# board.net
KiCad netlist of a schematic drawn in EAGLE
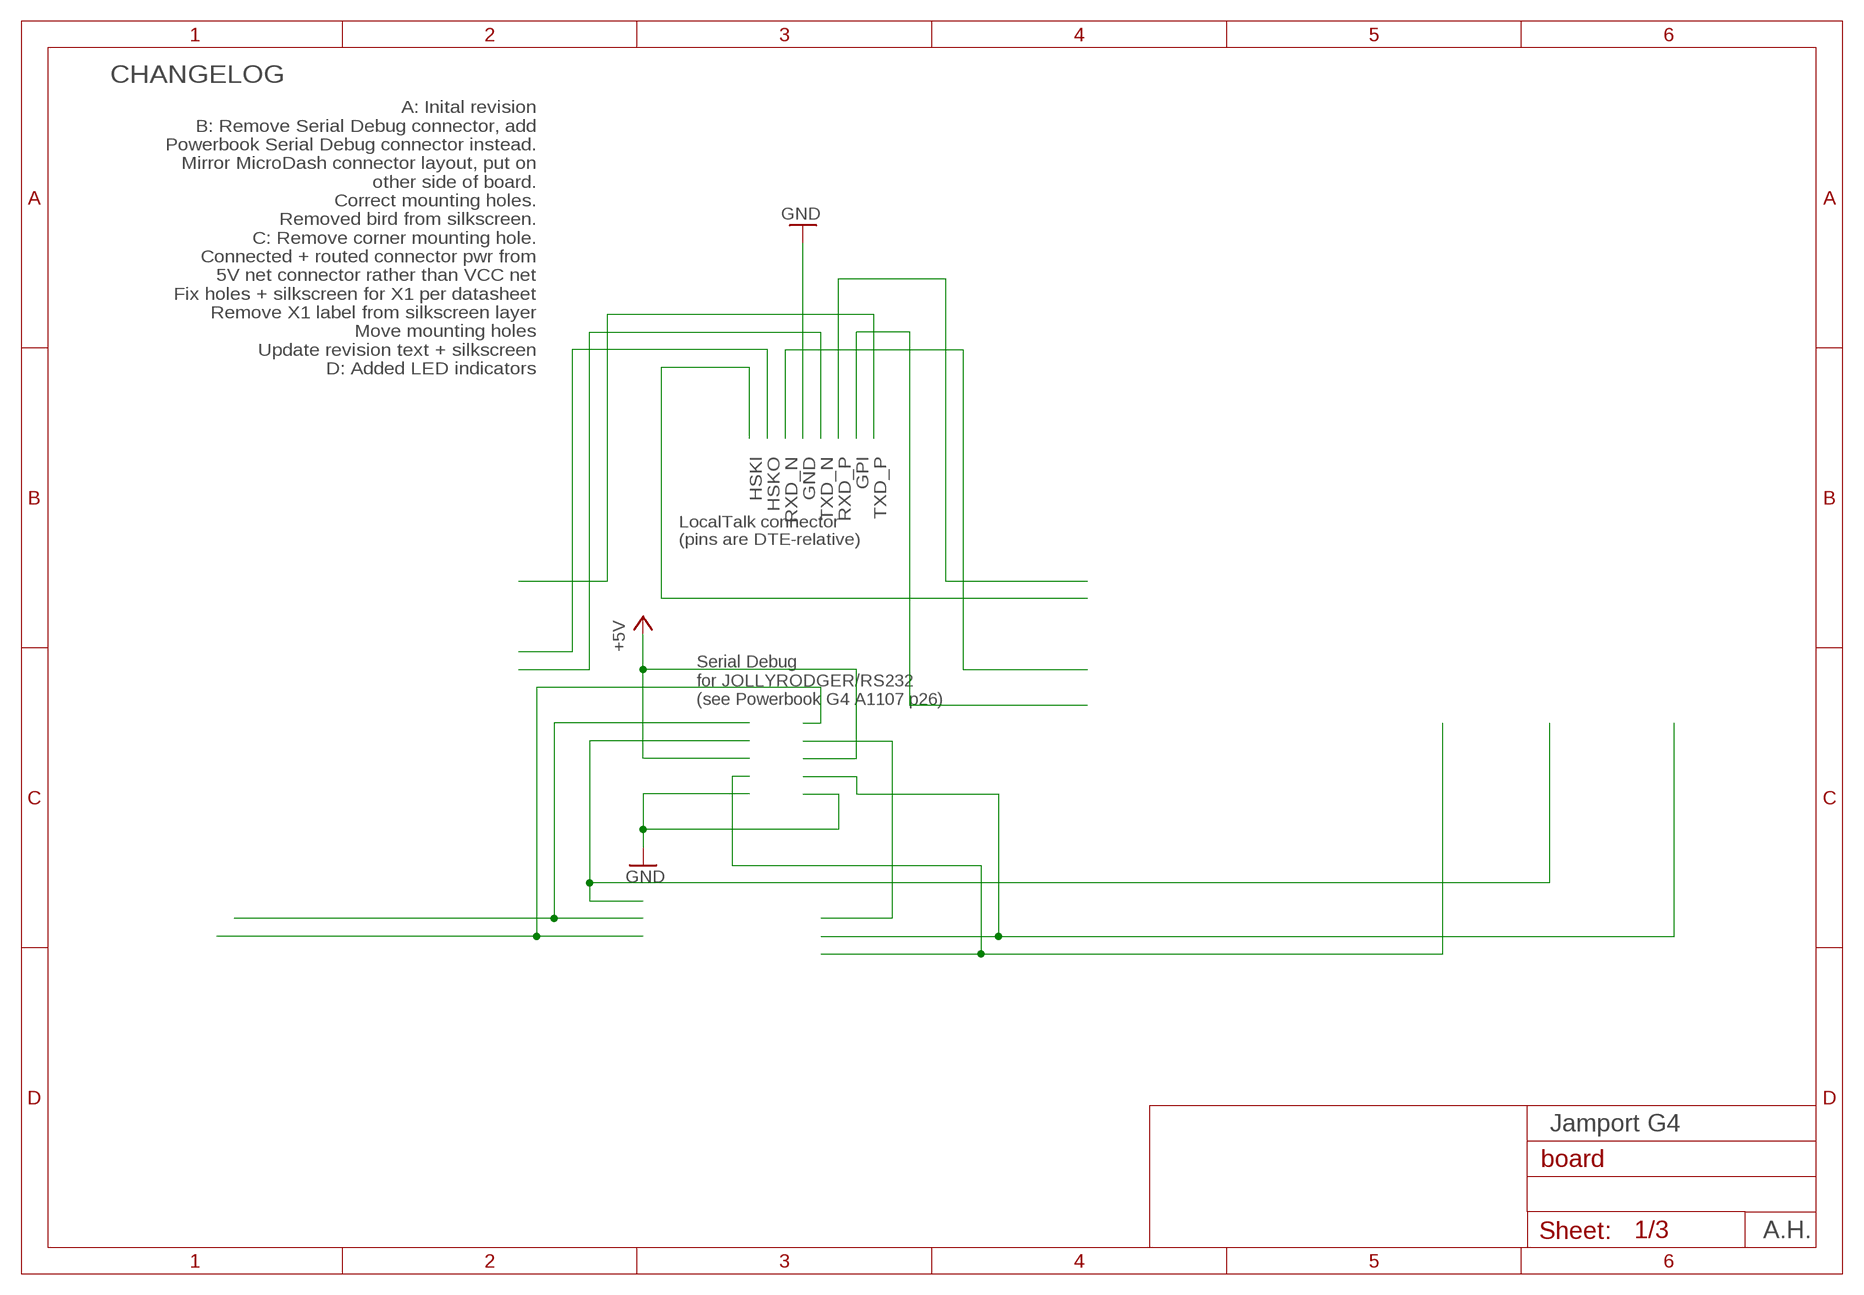
[diagram p0: schematic, sheet 1]
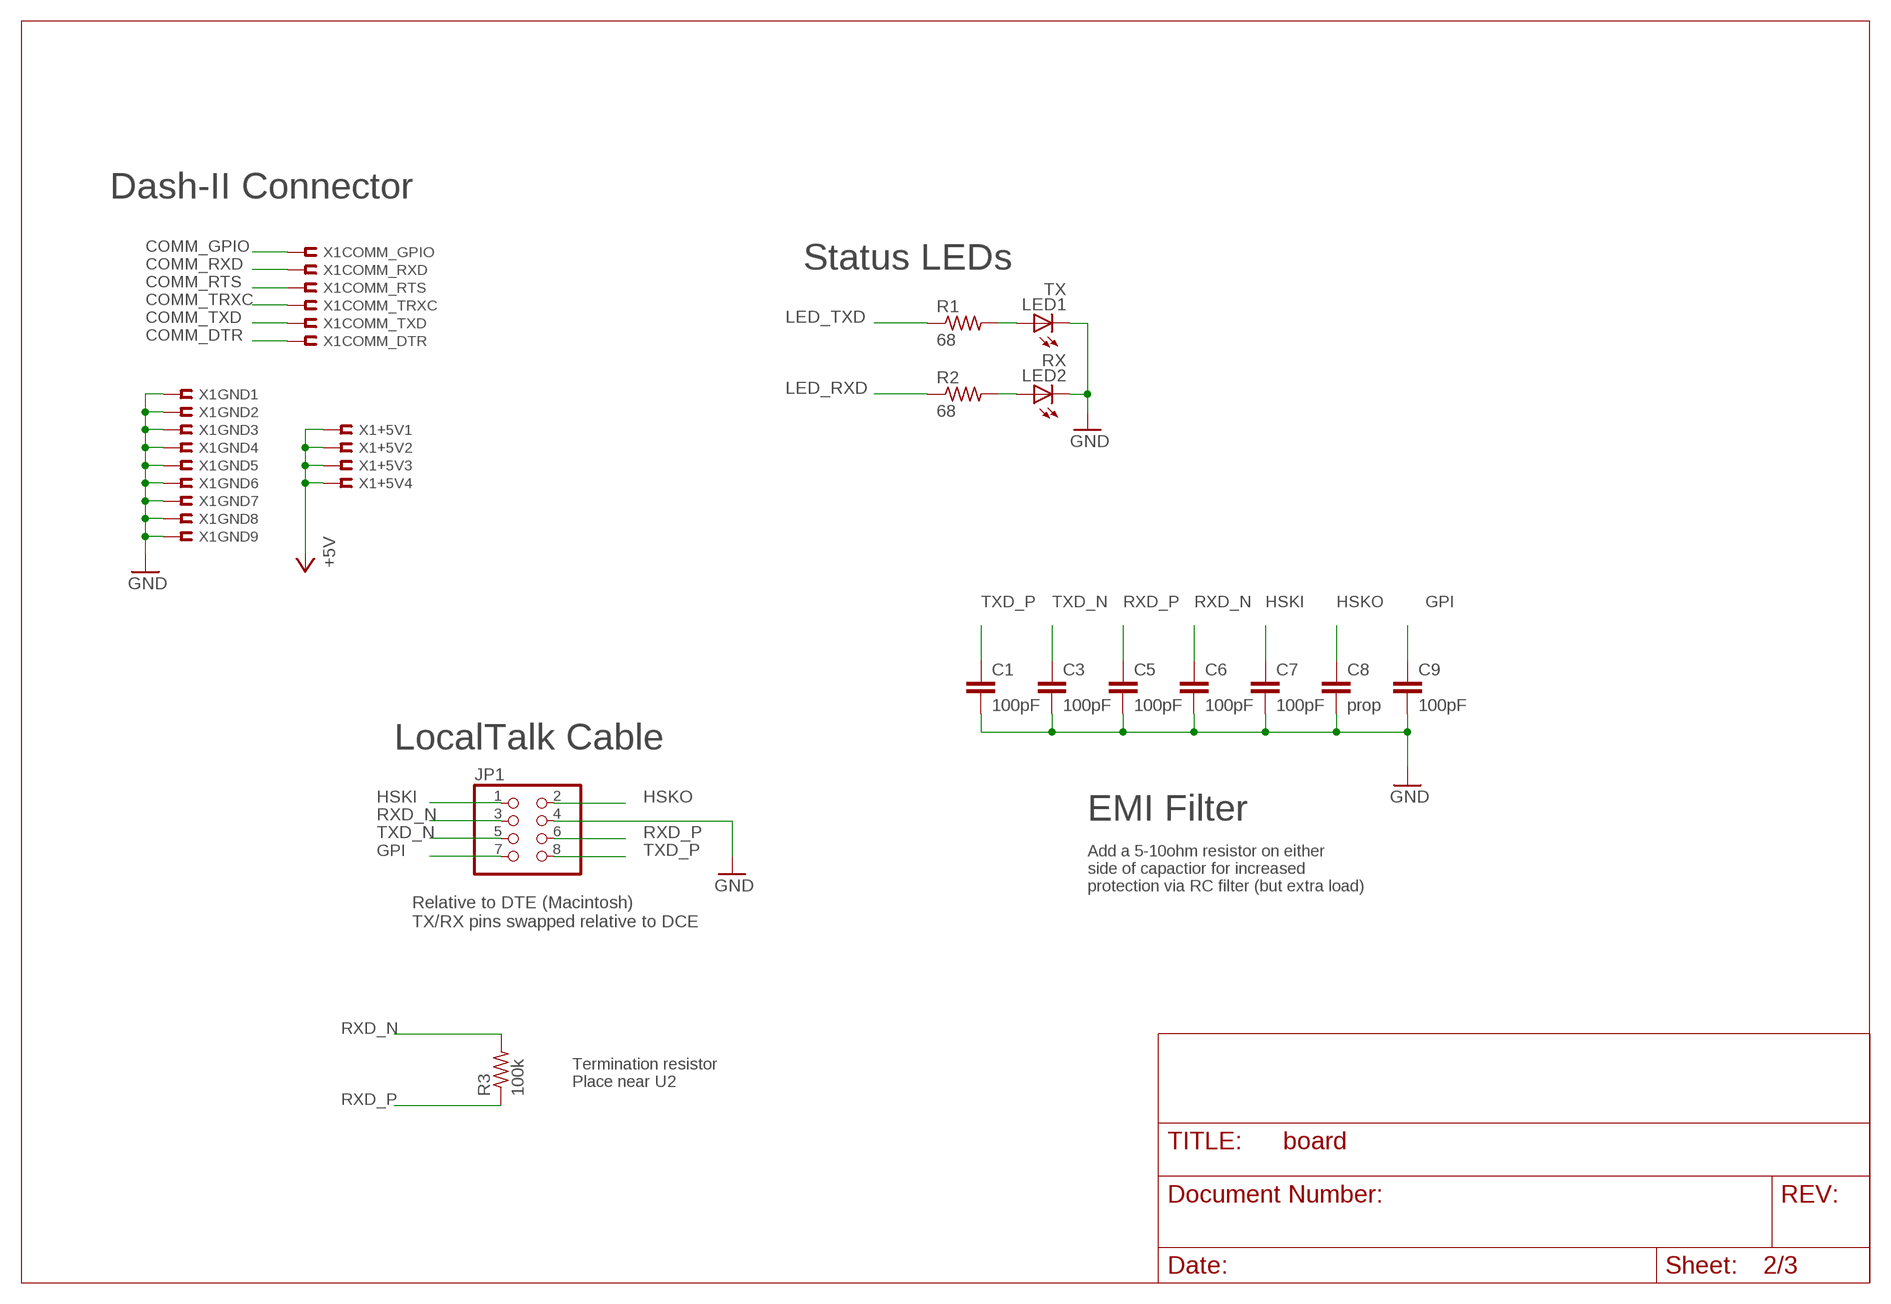
[diagram p1: schematic, sheet 2]
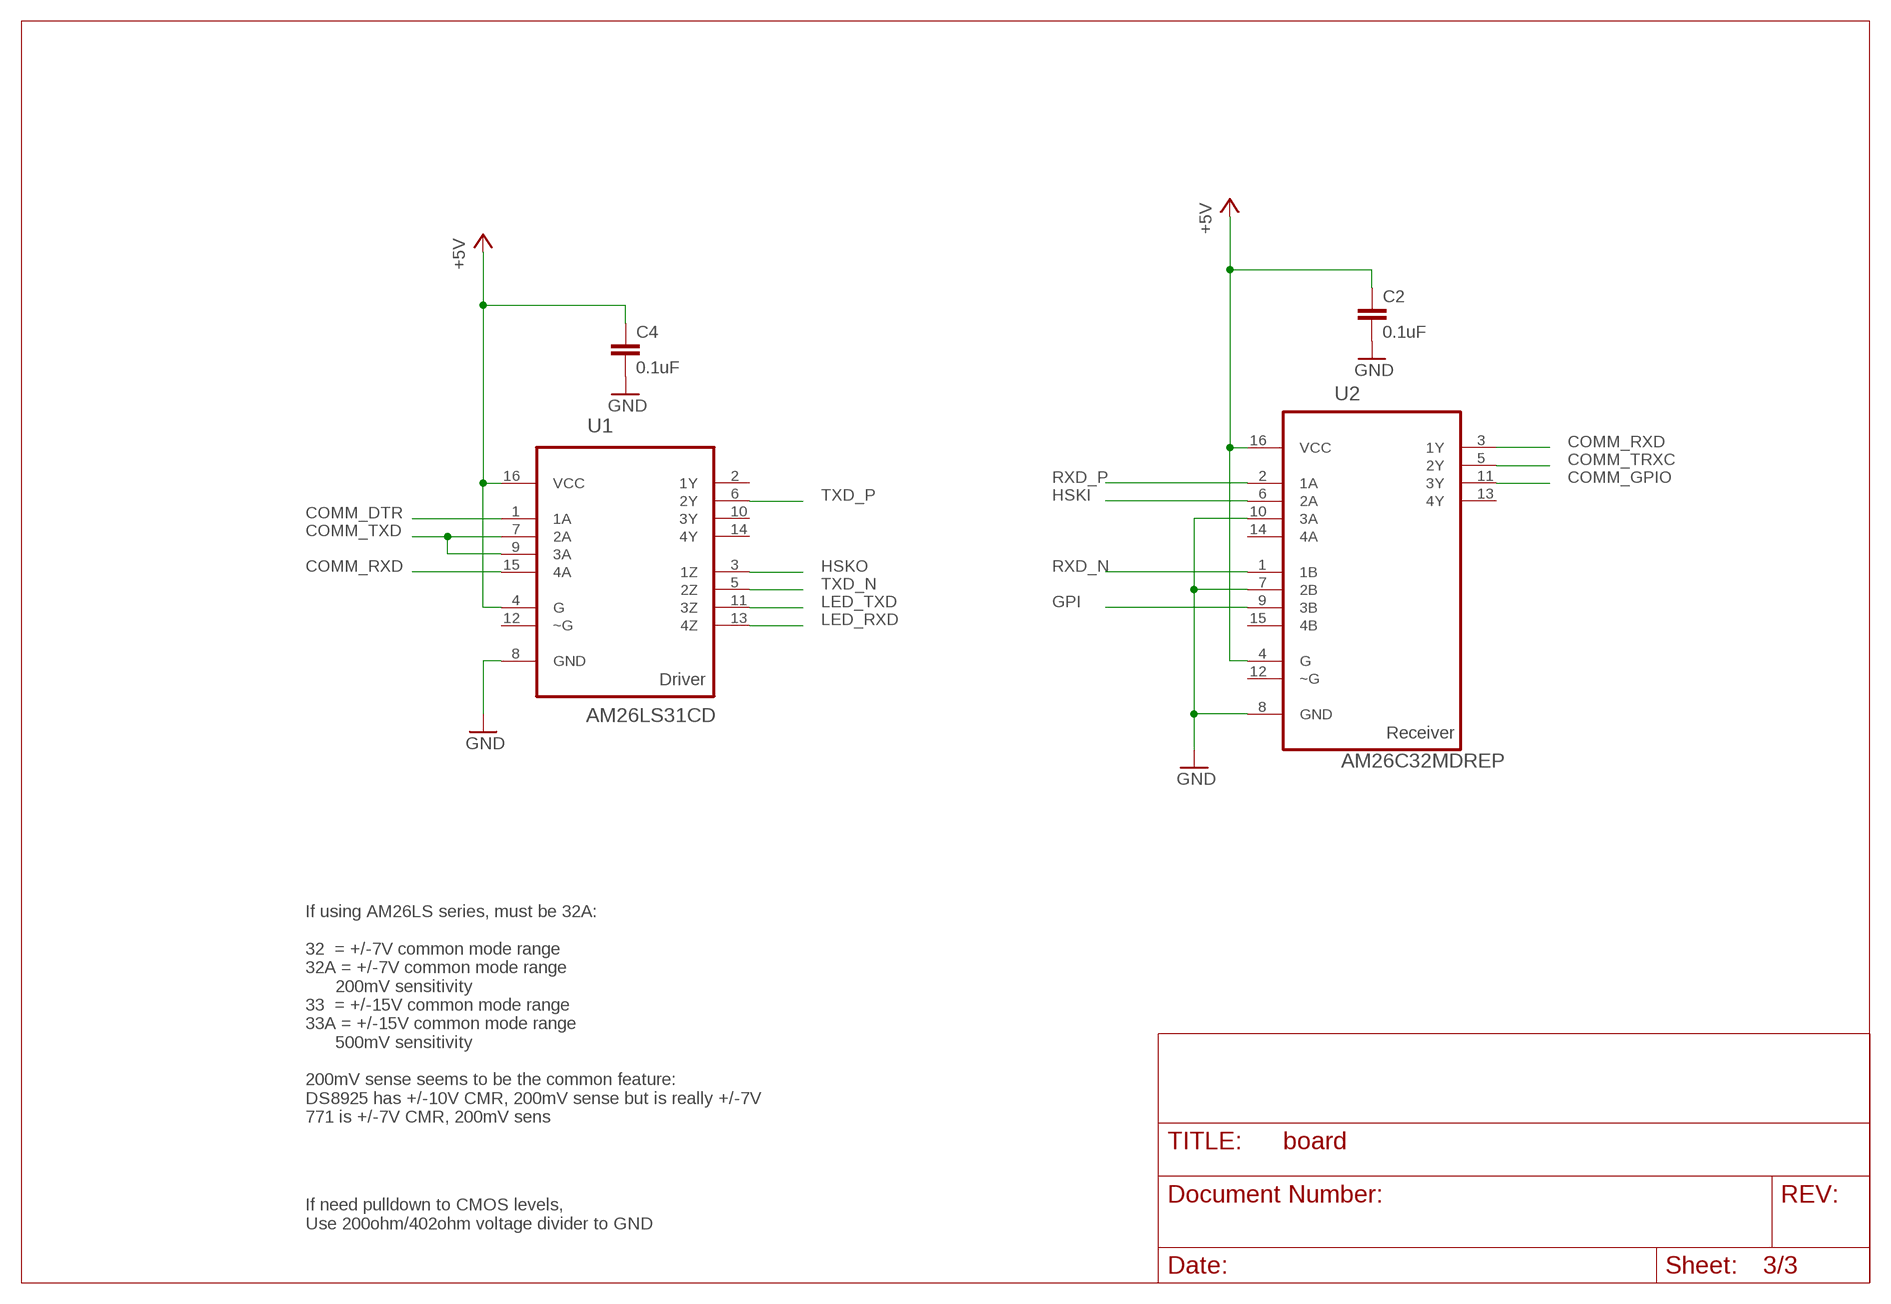
[diagram p2: schematic, sheet 3]

(export (version "E")
  (design (tool "Eeschema 10.0.6"))
  (components
    (comp (ref "C1")
      (value "100pF")
      (footprint "eagle-import:C0603")
      (libsource (lib "eagle-import") (part "C-EUC0603"))
    )
    (comp (ref "C3")
      (value "100pF")
      (footprint "eagle-import:C0603")
      (libsource (lib "eagle-import") (part "C-EUC0603"))
    )
    (comp (ref "C5")
      (value "100pF")
      (footprint "eagle-import:C0603")
      (libsource (lib "eagle-import") (part "C-EUC0603"))
    )
    (comp (ref "C6")
      (value "100pF")
      (footprint "eagle-import:C0603")
      (libsource (lib "eagle-import") (part "C-EUC0603"))
    )
    (comp (ref "C7")
      (value "100pF")
      (footprint "eagle-import:C0603")
      (libsource (lib "eagle-import") (part "C-EUC0603"))
    )
    (comp (ref "C8")
      (value "prop")
      (footprint "eagle-import:C0603")
      (libsource (lib "eagle-import") (part "C-EUC0603"))
    )
    (comp (ref "C9")
      (value "100pF")
      (footprint "eagle-import:C0603")
      (libsource (lib "eagle-import") (part "C-EUC0603"))
    )
    (comp (ref "JP1")
      (value "PINHD-2X4")
      (footprint "eagle-import:2X04")
      (libsource (lib "eagle-import") (part "PINHD-2X4"))
    )
    (comp (ref "LED1")
      (value "TX")
      (footprint "eagle-import:CHIPLED_1305")
      (libsource (lib "eagle-import") (part "HSM-C265E"))
    )
    (comp (ref "LED2")
      (value "RX")
      (footprint "eagle-import:CHIPLED_1305")
      (libsource (lib "eagle-import") (part "HSM-C265E"))
    )
    (comp (ref "R1")
      (value "68")
      (footprint "eagle-import:R0603")
      (libsource (lib "eagle-import") (part "R-US_R0603"))
    )
    (comp (ref "R2")
      (value "68")
      (footprint "eagle-import:R0603")
      (libsource (lib "eagle-import") (part "R-US_R0603"))
    )
    (comp (ref "R3")
      (value "100k")
      (footprint "eagle-import:R0603")
      (libsource (lib "eagle-import") (part "R-US_R0603"))
    )
    (comp (ref "X1")
      (value "55091-0409REV")
      (footprint "eagle-import:55091-0409-REV")
      (libsource (lib "eagle-import") (part "55091-0409REV"))
    )
    (comp (ref "C2")
      (value "0.1uF")
      (footprint "eagle-import:C0603")
      (libsource (lib "eagle-import") (part "resistor_C-EUC0603"))
    )
    (comp (ref "C4")
      (value "0.1uF")
      (footprint "eagle-import:C0603")
      (libsource (lib "eagle-import") (part "resistor_C-EUC0603"))
    )
    (comp (ref "U1")
      (value "AM26LS31CD")
      (footprint "eagle-import:SOIC127P600X175-16N")
      (libsource (lib "eagle-import") (part "AM26LS31CD"))
    )
    (comp (ref "U2")
      (value "AM26C32MDREP")
      (footprint "eagle-import:SOIC127P600X175-16N")
      (libsource (lib "eagle-import") (part "AM26C32MDREP"))
    )
  )
  (nets
    (net (code "1") (name "+5V") (class "Default")
      (node (ref "C2") (pin "1") (pinfunction "1_1") (pintype "passive"))
      (node (ref "C4") (pin "1") (pinfunction "1_1") (pintype "passive"))
      (node (ref "U1") (pin "16") (pinfunction "VCC_16") (pintype "power_in"))
      (node (ref "U1") (pin "4") (pinfunction "G_4") (pintype "input"))
      (node (ref "U2") (pin "16") (pinfunction "VCC_16") (pintype "power_in"))
      (node (ref "U2") (pin "4") (pinfunction "G_4") (pintype "input"))
      (node (ref "X1") (pin "37") (pinfunction "S_37") (pintype "passive"))
      (node (ref "X1") (pin "38") (pinfunction "S_38") (pintype "passive"))
      (node (ref "X1") (pin "39") (pinfunction "S_39") (pintype "passive"))
      (node (ref "X1") (pin "40") (pinfunction "S_40") (pintype "passive"))
    )
    (net (code "2") (name "COMM_DTR") (class "Default")
      (node (ref "U1") (pin "1") (pinfunction "1A_1") (pintype "input"))
      (node (ref "X1") (pin "9") (pinfunction "S_9") (pintype "passive"))
    )
    (net (code "3") (name "COMM_GPIO") (class "Default")
      (node (ref "U2") (pin "11") (pinfunction "3Y_11") (pintype "output"))
      (node (ref "X1") (pin "12") (pinfunction "S_12") (pintype "passive"))
    )
    (net (code "4") (name "COMM_RTS") (class "Default")
      (node (ref "X1") (pin "6") (pinfunction "S_6") (pintype "passive"))
    )
    (net (code "5") (name "COMM_RXD") (class "Default")
      (node (ref "U1") (pin "15") (pinfunction "4A_15") (pintype "input"))
      (node (ref "U2") (pin "3") (pinfunction "1Y_3") (pintype "output"))
      (node (ref "X1") (pin "10") (pinfunction "S_10") (pintype "passive"))
    )
    (net (code "6") (name "COMM_TRXC") (class "Default")
      (node (ref "U2") (pin "5") (pinfunction "2Y_5") (pintype "output"))
      (node (ref "X1") (pin "15") (pinfunction "S_15") (pintype "passive"))
    )
    (net (code "7") (name "COMM_TXD") (class "Default")
      (node (ref "U1") (pin "7") (pinfunction "2A_7") (pintype "input"))
      (node (ref "U1") (pin "9") (pinfunction "3A_9") (pintype "input"))
      (node (ref "X1") (pin "13") (pinfunction "S_13") (pintype "passive"))
    )
    (net (code "8") (name "GND") (class "Default")
      (node (ref "C1") (pin "2") (pinfunction "2_2") (pintype "passive"))
      (node (ref "C2") (pin "2") (pinfunction "2_2") (pintype "passive"))
      (node (ref "C3") (pin "2") (pinfunction "2_2") (pintype "passive"))
      (node (ref "C4") (pin "2") (pinfunction "2_2") (pintype "passive"))
      (node (ref "C5") (pin "2") (pinfunction "2_2") (pintype "passive"))
      (node (ref "C6") (pin "2") (pinfunction "2_2") (pintype "passive"))
      (node (ref "C7") (pin "2") (pinfunction "2_2") (pintype "passive"))
      (node (ref "C8") (pin "2") (pinfunction "2_2") (pintype "passive"))
      (node (ref "C9") (pin "2") (pinfunction "2_2") (pintype "passive"))
      (node (ref "JP1") (pin "4") (pinfunction "4_4") (pintype "passive"))
      (node (ref "LED1") (pin "C") (pinfunction "C_C") (pintype "passive"))
      (node (ref "LED2") (pin "C") (pinfunction "C_C") (pintype "passive"))
      (node (ref "U1") (pin "8") (pinfunction "GND_8") (pintype "passive"))
      (node (ref "U2") (pin "10") (pinfunction "3A_10") (pintype "input"))
      (node (ref "U2") (pin "7") (pinfunction "2B_7") (pintype "input"))
      (node (ref "U2") (pin "8") (pinfunction "GND_8") (pintype "passive"))
      (node (ref "X1") (pin "11") (pinfunction "S_11") (pintype "passive"))
      (node (ref "X1") (pin "14") (pinfunction "S_14") (pintype "passive"))
      (node (ref "X1") (pin "17") (pinfunction "S_17") (pintype "passive"))
      (node (ref "X1") (pin "22") (pinfunction "S_22") (pintype "passive"))
      (node (ref "X1") (pin "25") (pinfunction "S_25") (pintype "passive"))
      (node (ref "X1") (pin "28") (pinfunction "S_28") (pintype "passive"))
      (node (ref "X1") (pin "31") (pinfunction "S_31") (pintype "passive"))
      (node (ref "X1") (pin "33") (pinfunction "S_33") (pintype "passive"))
      (node (ref "X1") (pin "8") (pinfunction "S_8") (pintype "passive"))
    )
    (net (code "9") (name "GPI") (class "Default")
      (node (ref "C9") (pin "1") (pinfunction "1_1") (pintype "passive"))
      (node (ref "JP1") (pin "7") (pinfunction "7_7") (pintype "passive"))
      (node (ref "U2") (pin "9") (pinfunction "3B_9") (pintype "input"))
    )
    (net (code "10") (name "HSKI") (class "Default")
      (node (ref "C7") (pin "1") (pinfunction "1_1") (pintype "passive"))
      (node (ref "JP1") (pin "1") (pinfunction "1_1") (pintype "passive"))
      (node (ref "U2") (pin "6") (pinfunction "2A_6") (pintype "input"))
    )
    (net (code "11") (name "HSKO") (class "Default")
      (node (ref "C8") (pin "1") (pinfunction "1_1") (pintype "passive"))
      (node (ref "JP1") (pin "2") (pinfunction "2_2") (pintype "passive"))
      (node (ref "U1") (pin "3") (pinfunction "1Z_3") (pintype "output"))
    )
    (net (code "12") (name "LED_RXD") (class "Default")
      (node (ref "R2") (pin "1") (pinfunction "1_1") (pintype "passive"))
      (node (ref "U1") (pin "13") (pinfunction "4Z_13") (pintype "output"))
    )
    (net (code "13") (name "LED_TXD") (class "Default")
      (node (ref "R1") (pin "1") (pinfunction "1_1") (pintype "passive"))
      (node (ref "U1") (pin "11") (pinfunction "3Z_11") (pintype "output"))
    )
    (net (code "14") (name "Net-(LED1-PadA)") (class "Default")
      (node (ref "LED1") (pin "A") (pinfunction "A_A") (pintype "passive"))
      (node (ref "R1") (pin "2") (pinfunction "2_2") (pintype "passive"))
    )
    (net (code "15") (name "Net-(LED2-PadA)") (class "Default")
      (node (ref "LED2") (pin "A") (pinfunction "A_A") (pintype "passive"))
      (node (ref "R2") (pin "2") (pinfunction "2_2") (pintype "passive"))
    )
    (net (code "16") (name "RXD_N") (class "Default")
      (node (ref "C6") (pin "1") (pinfunction "1_1") (pintype "passive"))
      (node (ref "JP1") (pin "3") (pinfunction "3_3") (pintype "passive"))
      (node (ref "R3") (pin "2") (pinfunction "2_2") (pintype "passive"))
      (node (ref "U2") (pin "1") (pinfunction "1B_1") (pintype "input"))
    )
    (net (code "17") (name "RXD_P") (class "Default")
      (node (ref "C5") (pin "1") (pinfunction "1_1") (pintype "passive"))
      (node (ref "JP1") (pin "6") (pinfunction "6_6") (pintype "passive"))
      (node (ref "R3") (pin "1") (pinfunction "1_1") (pintype "passive"))
      (node (ref "U2") (pin "2") (pinfunction "1A_2") (pintype "input"))
    )
    (net (code "18") (name "TXD_N") (class "Default")
      (node (ref "C3") (pin "1") (pinfunction "1_1") (pintype "passive"))
      (node (ref "JP1") (pin "5") (pinfunction "5_5") (pintype "passive"))
      (node (ref "U1") (pin "5") (pinfunction "2Z_5") (pintype "output"))
    )
    (net (code "19") (name "TXD_P") (class "Default")
      (node (ref "C1") (pin "1") (pinfunction "1_1") (pintype "passive"))
      (node (ref "JP1") (pin "8") (pinfunction "8_8") (pintype "passive"))
      (node (ref "U1") (pin "6") (pinfunction "2Y_6") (pintype "output"))
    )
    (net (code "20") (name "unconnected-(U1-1Y-Pad2)") (class "Default")
      (node (ref "U1") (pin "2") (pinfunction "1Y_2") (pintype "output"))
    )
    (net (code "21") (name "unconnected-(U1-3Y-Pad10)") (class "Default")
      (node (ref "U1") (pin "10") (pinfunction "3Y_10") (pintype "output"))
    )
    (net (code "22") (name "unconnected-(U1-4Y-Pad14)") (class "Default")
      (node (ref "U1") (pin "14") (pinfunction "4Y_14") (pintype "output"))
    )
    (net (code "23") (name "unconnected-(U1-~{G}-Pad12)") (class "Default")
      (node (ref "U1") (pin "12") (pinfunction "~{G}_12") (pintype "input"))
    )
    (net (code "24") (name "unconnected-(U2-4A-Pad14)") (class "Default")
      (node (ref "U2") (pin "14") (pinfunction "4A_14") (pintype "input"))
    )
    (net (code "25") (name "unconnected-(U2-4B-Pad15)") (class "Default")
      (node (ref "U2") (pin "15") (pinfunction "4B_15") (pintype "input"))
    )
    (net (code "26") (name "unconnected-(U2-4Y-Pad13)") (class "Default")
      (node (ref "U2") (pin "13") (pinfunction "4Y_13") (pintype "output"))
    )
    (net (code "27") (name "unconnected-(U2-~{G}-Pad12)") (class "Default")
      (node (ref "U2") (pin "12") (pinfunction "~{G}_12") (pintype "input"))
    )
  )
)
